# ac_to_dc.net
KiCad netlist of a schematic drawn in EAGLE
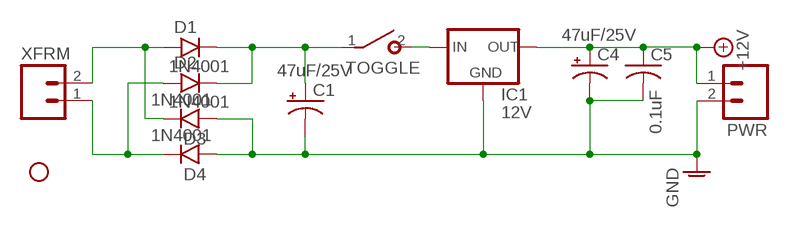
[diagram p0: schematic, sheet 1]

(export (version "E")
  (design (tool "Eeschema 10.0.6"))
  (components
    (comp (ref "C1")
      (value "47uF/25V")
      (footprint "eagle-import:E2,5-6")
      (libsource (lib "eagle-import") (part "CPOL-USE2.5-6"))
    )
    (comp (ref "C4")
      (value "47uF/25V")
      (footprint "eagle-import:E2,5-6")
      (libsource (lib "eagle-import") (part "CPOL-USE2.5-6"))
    )
    (comp (ref "C5")
      (value "0.1uF")
      (footprint "eagle-import:C025-025X050")
      (libsource (lib "eagle-import") (part "C-US025-025X050"))
    )
    (comp (ref "D1")
      (value "1N4001")
      (footprint "eagle-import:DO41-3")
      (libsource (lib "eagle-import") (part "1N400X.3"))
    )
    (comp (ref "D2")
      (value "1N4001")
      (footprint "eagle-import:DO41-3")
      (libsource (lib "eagle-import") (part "1N400X.3"))
    )
    (comp (ref "D3")
      (value "1N4001")
      (footprint "eagle-import:DO41-3")
      (libsource (lib "eagle-import") (part "1N400X.3"))
    )
    (comp (ref "D4")
      (value "1N4001")
      (footprint "eagle-import:DO41-3")
      (libsource (lib "eagle-import") (part "1N400X.3"))
    )
    (comp (ref "IC1")
      (value "12V")
      (footprint "eagle-import:78XXS")
      (libsource (lib "eagle-import") (part "78XXS"))
    )
    (comp (ref "JP1")
      (value "STAND-OFF")
      (footprint "eagle-import:STAND-OFF")
      (libsource (lib "eagle-import") (part "STAND-OFF"))
    )
    (comp (ref "PWR")
      (value "M02PTH")
      (footprint "eagle-import:1X02")
      (libsource (lib "eagle-import") (part "M02PTH"))
    )
    (comp (ref "TOGGLE")
      (value "SPST")
      (footprint "eagle-import:SPST")
      (libsource (lib "eagle-import") (part "SPST"))
    )
    (comp (ref "XFRM")
      (value "M02PTH")
      (footprint "eagle-import:1X02")
      (libsource (lib "eagle-import") (part "M02PTH"))
    )
  )
  (nets
    (net (code "1") (name "+12V") (class "Default")
      (node (ref "C4") (pin "+") (pinfunction "+_+") (pintype "passive"))
      (node (ref "C5") (pin "1") (pinfunction "1_1") (pintype "passive"))
      (node (ref "IC1") (pin "OUT") (pinfunction "OUT_OUT") (pintype "passive"))
      (node (ref "PWR") (pin "1") (pinfunction "1_1") (pintype "passive"))
    )
    (net (code "2") (name "GND") (class "Default")
      (node (ref "C1") (pin "-") (pinfunction "-_-") (pintype "passive"))
      (node (ref "C4") (pin "-") (pinfunction "-_-") (pintype "passive"))
      (node (ref "C5") (pin "2") (pinfunction "2_2") (pintype "passive"))
      (node (ref "D3") (pin "A") (pinfunction "A_A") (pintype "passive"))
      (node (ref "D4") (pin "A") (pinfunction "A_A") (pintype "passive"))
      (node (ref "IC1") (pin "GND") (pinfunction "GND_GND") (pintype "input"))
      (node (ref "PWR") (pin "2") (pinfunction "2_2") (pintype "passive"))
    )
    (net (code "3") (name "Net-(D1-PadA)") (class "Default")
      (node (ref "D1") (pin "A") (pinfunction "A_A") (pintype "passive"))
      (node (ref "D3") (pin "C") (pinfunction "C_C") (pintype "passive"))
      (node (ref "XFRM") (pin "2") (pinfunction "2_2") (pintype "passive"))
    )
    (net (code "4") (name "Net-(D2-PadA)") (class "Default")
      (node (ref "D2") (pin "A") (pinfunction "A_A") (pintype "passive"))
      (node (ref "D4") (pin "C") (pinfunction "C_C") (pintype "passive"))
      (node (ref "XFRM") (pin "1") (pinfunction "1_1") (pintype "passive"))
    )
    (net (code "5") (name "Net-(TOGGLE-P)") (class "Default")
      (node (ref "C1") (pin "+") (pinfunction "+_+") (pintype "passive"))
      (node (ref "D1") (pin "C") (pinfunction "C_C") (pintype "passive"))
      (node (ref "D2") (pin "C") (pinfunction "C_C") (pintype "passive"))
      (node (ref "TOGGLE") (pin "1") (pinfunction "P_1") (pintype "passive"))
    )
    (net (code "6") (name "Net-(TOGGLE-S)") (class "Default")
      (node (ref "IC1") (pin "IN") (pinfunction "IN_IN") (pintype "input"))
      (node (ref "TOGGLE") (pin "2") (pinfunction "S_2") (pintype "passive"))
    )
  )
)
